# SCH_YDS-Charger_2022-05-27.net
KiCad netlist of a schematic drawn in EasyEDA
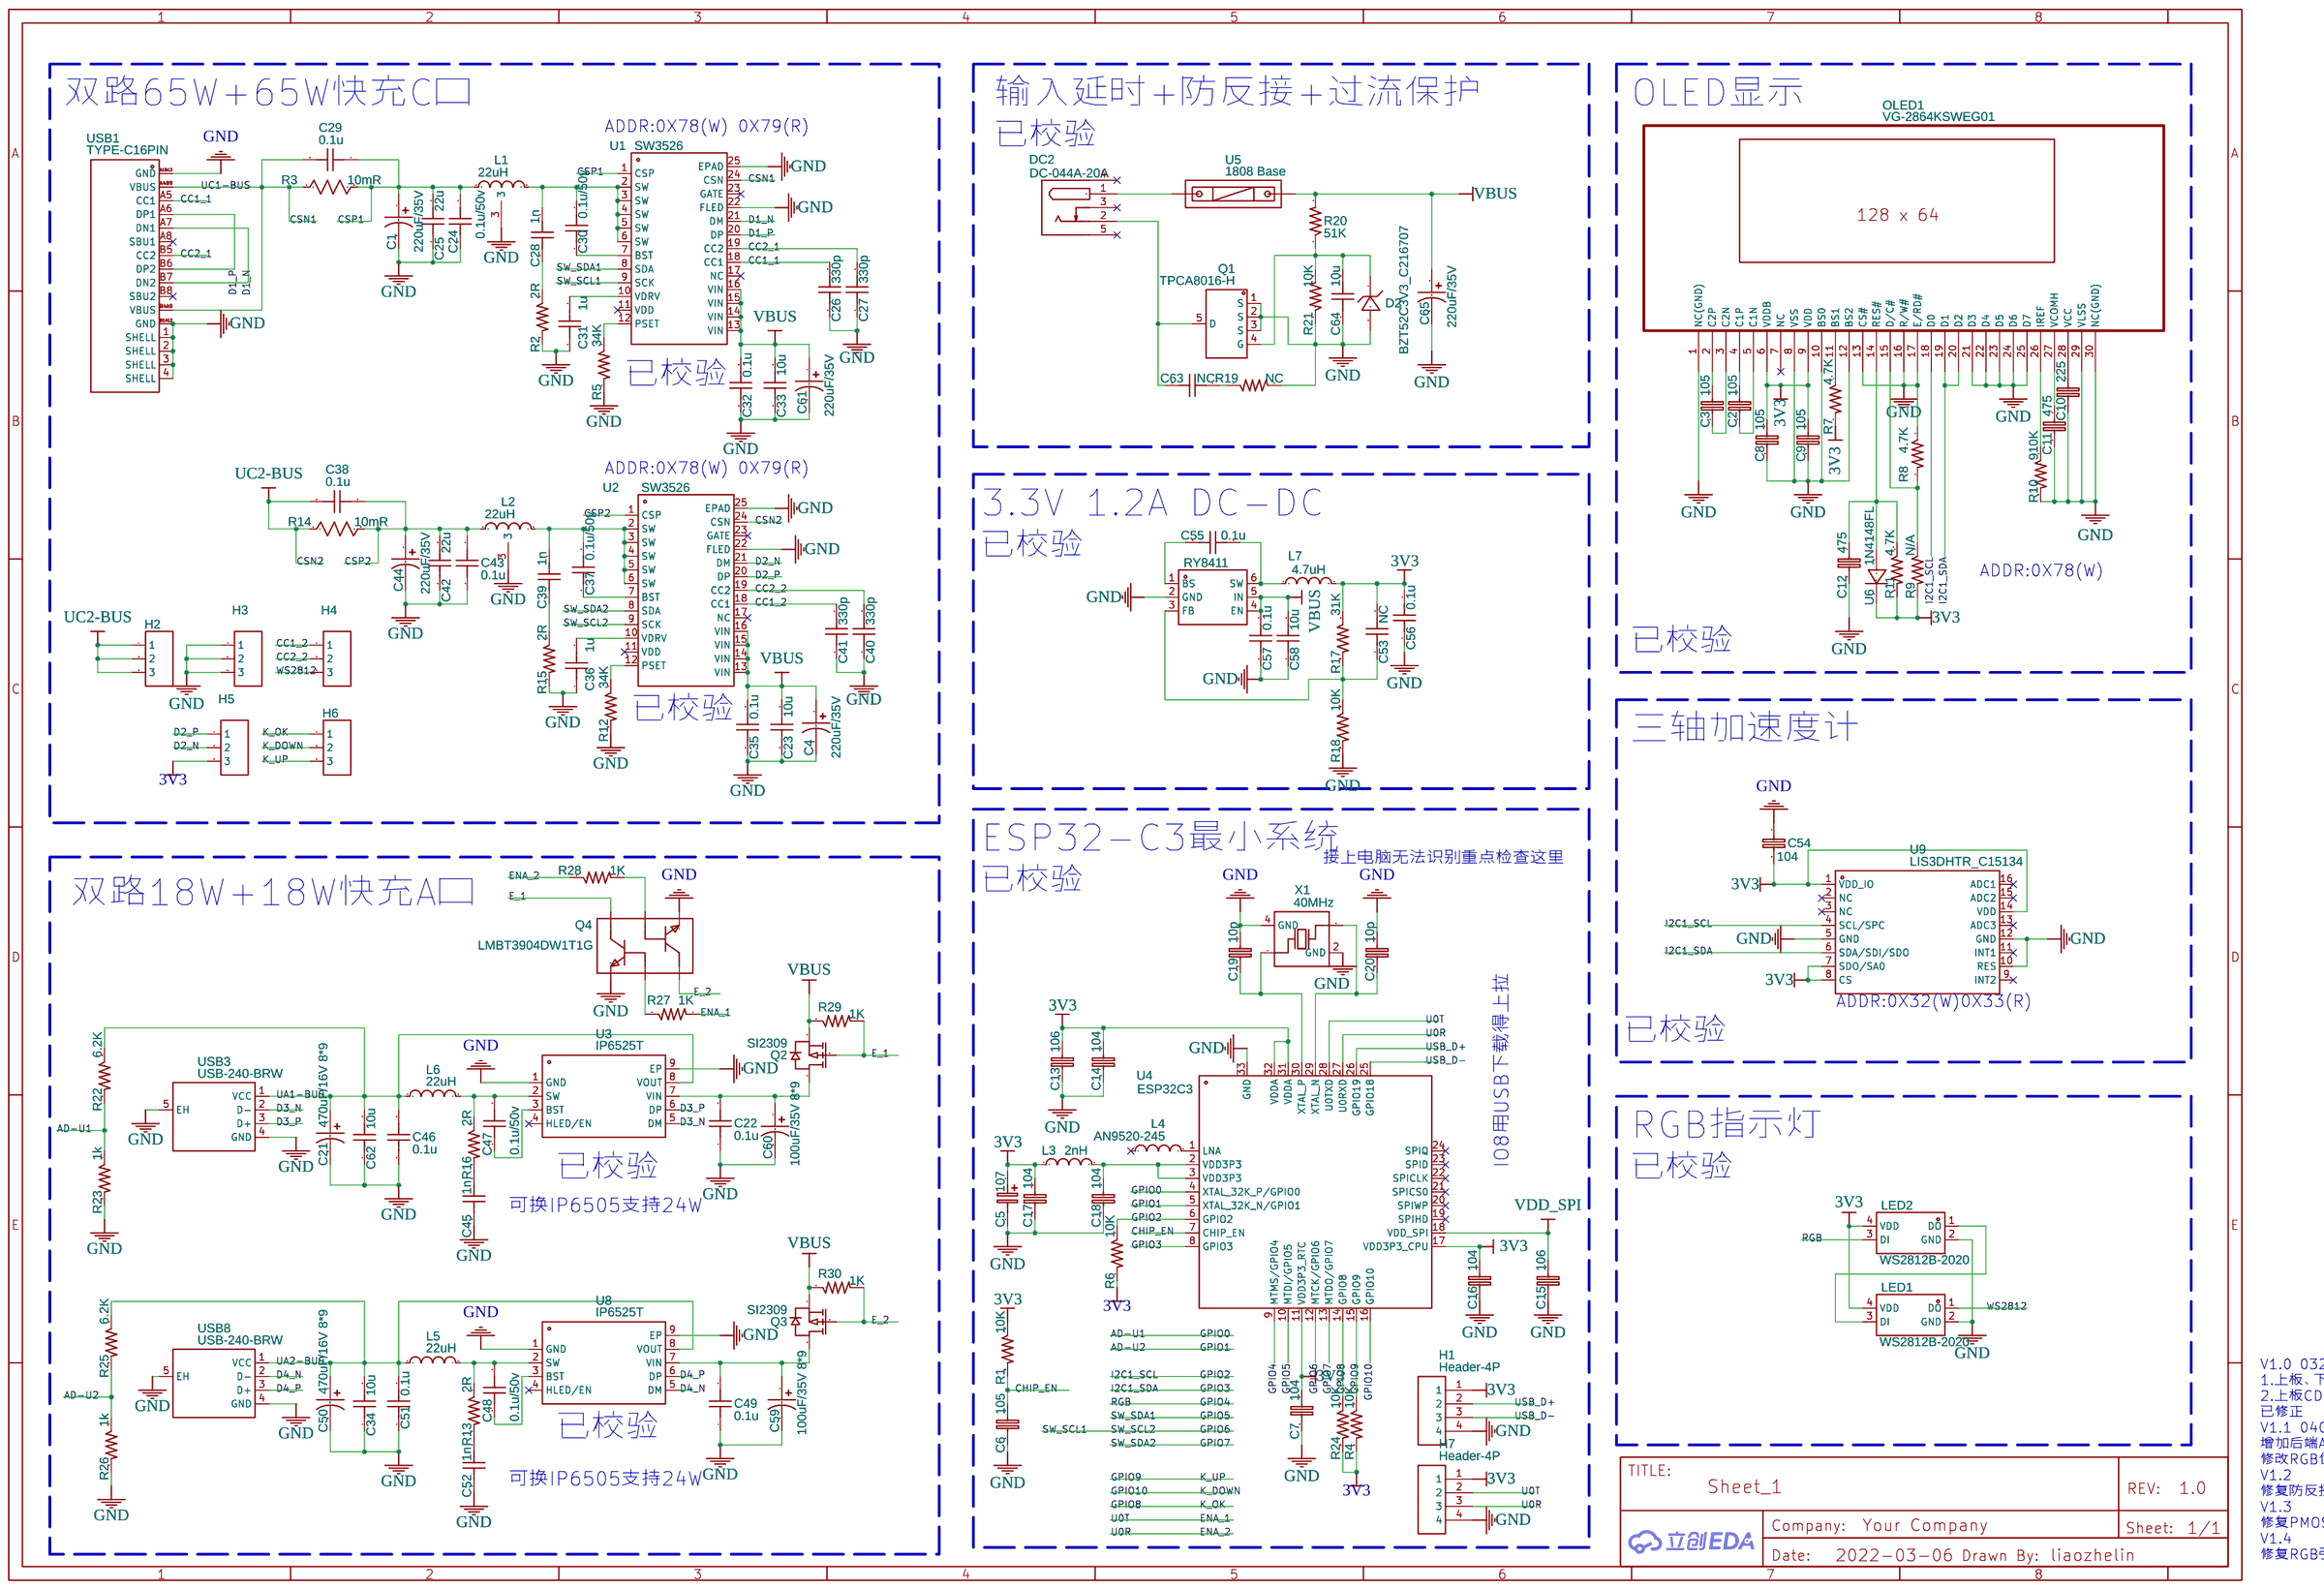
[diagram p0: schematic sheet]

(export (version "E")
  (design (tool "Eeschema 10.0.6"))
  (components
    (comp (ref "BS")
      (value "RY8411")
      (fields (field (name "BOM_Supplier Part") "C9900000347"))
      (libsource (lib "") (part "RY8411"))
    )
    (comp (ref "C1")
      (value "220uF/35V")
      (fields
        (field (name "BOM_Manufacturer Part") "BC016M821LO8*12L-1A4T")
        (field (name "BOM_Supplier Part") "C516110")
      )
      (libsource (lib "") (part "BC016M821LO8*12L-1A4T_1"))
    )
    (comp (ref "C2") (value "105") (libsource (lib "") (part "1.0PF-50V(-_+.25PF)(0603)")))
    (comp (ref "C3") (value "105") (libsource (lib "") (part "1.0PF-50V(-_+.25PF)(0603)")))
    (comp (ref "C4")
      (value "220uF/35V")
      (fields
        (field (name "BOM_Manufacturer Part") "BC016M821LO8*12L-1A4T")
        (field (name "BOM_Supplier Part") "C516110")
      )
      (libsource (lib "") (part "BC016M821LO8*12L-1A4T_1"))
    )
    (comp (ref "C5") (value "107") (libsource (lib "") (part "C_Tan_SMD_B_EU")))
    (comp (ref "C6") (value "105") (libsource (lib "") (part "1.0PF-50V(-_+.25PF)(0603)")))
    (comp (ref "C7") (value "104") (libsource (lib "") (part "1.0PF-50V(-_+.25PF)(0603)")))
    (comp (ref "C8") (value "105") (libsource (lib "") (part "1.0PF-50V(-_+.25PF)(0603)")))
    (comp (ref "C9") (value "105") (libsource (lib "") (part "1.0PF-50V(-_+.25PF)(0603)")))
    (comp (ref "C10") (value "225") (libsource (lib "") (part "1.0PF-50V(-_+.25PF)(0603)")))
    (comp (ref "C11") (value "475") (libsource (lib "") (part "1.0PF-50V(-_+.25PF)(0603)")))
    (comp (ref "C12") (value "475") (libsource (lib "") (part "1.0PF-50V(-_+.25PF)(0603)")))
    (comp (ref "C13") (value "106") (libsource (lib "") (part "1.0PF-50V(-_+.25PF)(0603)")))
    (comp (ref "C14") (value "104") (libsource (lib "") (part "1.0PF-50V(-_+.25PF)(0603)")))
    (comp (ref "C15") (value "106") (libsource (lib "") (part "1.0PF-50V(-_+.25PF)(0603)")))
    (comp (ref "C16") (value "104") (libsource (lib "") (part "1.0PF-50V(-_+.25PF)(0603)")))
    (comp (ref "C17") (value "104") (libsource (lib "") (part "1.0PF-50V(-_+.25PF)(0603)")))
    (comp (ref "C18") (value "104") (libsource (lib "") (part "1.0PF-50V(-_+.25PF)(0603)")))
    (comp (ref "C19") (value "10p") (libsource (lib "") (part "1.0PF-50V(-_+.25PF)(0603)")))
    (comp (ref "C20") (value "10p") (libsource (lib "") (part "1.0PF-50V(-_+.25PF)(0603)")))
    (comp (ref "C21")
      (value "470uF/16V 8*9")
      (fields
        (field (name "BOM_Manufacturer Part") "BC016M821LO8*12L-1A4T")
        (field (name "BOM_Supplier Part") "C516110")
      )
      (libsource (lib "") (part "BC016M821LO8*12L-1A4T"))
    )
    (comp (ref "C22") (value "0.1u") (libsource (lib "") (part "C_0805_US")))
    (comp (ref "C23") (value "10u") (libsource (lib "") (part "C_0805_US")))
    (comp (ref "C24") (value "0.1u/50v") (libsource (lib "") (part "C_0805_US")))
    (comp (ref "C25") (value "22u") (libsource (lib "") (part "C_0805_US")))
    (comp (ref "C26") (value "330p") (libsource (lib "") (part "C_0805_US")))
    (comp (ref "C27") (value "330p") (libsource (lib "") (part "C_0805_US")))
    (comp (ref "C28") (value "1n") (libsource (lib "") (part "C_0805_US")))
    (comp (ref "C29") (value "0.1u") (libsource (lib "") (part "C_0805_US_1")))
    (comp (ref "C30") (value "0.1u/50v") (libsource (lib "") (part "C_0805_US")))
    (comp (ref "C31") (value "1u") (libsource (lib "") (part "C_0805_US")))
    (comp (ref "C32") (value "0.1u") (libsource (lib "") (part "C_0805_US")))
    (comp (ref "C33") (value "10u") (libsource (lib "") (part "C_0805_US")))
    (comp (ref "C34") (value "10u") (libsource (lib "") (part "C_0805_US")))
    (comp (ref "C35") (value "0.1u") (libsource (lib "") (part "C_0805_US")))
    (comp (ref "C36") (value "1u") (libsource (lib "") (part "C_0805_US")))
    (comp (ref "C37") (value "0.1u/50v") (libsource (lib "") (part "C_0805_US")))
    (comp (ref "C38") (value "0.1u") (libsource (lib "") (part "C_0805_US_1")))
    (comp (ref "C39") (value "1n") (libsource (lib "") (part "C_0805_US")))
    (comp (ref "C40") (value "330p") (libsource (lib "") (part "C_0805_US")))
    (comp (ref "C41") (value "330p") (libsource (lib "") (part "C_0805_US")))
    (comp (ref "C42") (value "22u") (libsource (lib "") (part "C_0805_US")))
    (comp (ref "C43") (value "0.1u") (libsource (lib "") (part "C_0805_US")))
    (comp (ref "C44")
      (value "220uF/35V")
      (fields
        (field (name "BOM_Manufacturer Part") "BC016M821LO8*12L-1A4T")
        (field (name "BOM_Supplier Part") "C516110")
      )
      (libsource (lib "") (part "BC016M821LO8*12L-1A4T_1"))
    )
    (comp (ref "C45") (value "1n") (libsource (lib "") (part "C_0805_US")))
    (comp (ref "C46") (value "0.1u") (libsource (lib "") (part "C_0805_US")))
    (comp (ref "C47") (value "0.1u/50v") (libsource (lib "") (part "C_0805_US")))
    (comp (ref "C48") (value "0.1u/50v") (libsource (lib "") (part "C_0805_US")))
    (comp (ref "C49") (value "0.1u") (libsource (lib "") (part "C_0805_US")))
    (comp (ref "C50")
      (value "470uF/16V 8*9")
      (fields
        (field (name "BOM_Manufacturer Part") "BC016M821LO8*12L-1A4T")
        (field (name "BOM_Supplier Part") "C516110")
      )
      (libsource (lib "") (part "BC016M821LO8*12L-1A4T"))
    )
    (comp (ref "C51") (value "0.1u") (libsource (lib "") (part "C_0805_US")))
    (comp (ref "C52") (value "1n") (libsource (lib "") (part "C_0805_US")))
    (comp (ref "C53") (value "NC") (libsource (lib "") (part "C_0805_US")))
    (comp (ref "C54") (value "104") (libsource (lib "") (part "1.0PF-50V(-_+.25PF)(0603)")))
    (comp (ref "C55") (value "0.1u") (libsource (lib "") (part "C_0805_US_1")))
    (comp (ref "C56") (value "0.1u") (libsource (lib "") (part "C_0805_US")))
    (comp (ref "C57") (value "0.1u") (libsource (lib "") (part "C_0805_US_2")))
    (comp (ref "C58") (value "10u") (libsource (lib "") (part "C_0805_US")))
    (comp (ref "C59")
      (value "100uF/35V 8*9")
      (fields
        (field (name "BOM_Manufacturer Part") "BC016M821LO8*12L-1A4T")
        (field (name "BOM_Supplier Part") "C516110")
      )
      (libsource (lib "") (part "BC016M821LO8*12L-1A4T_2"))
    )
    (comp (ref "C60")
      (value "100uF/35V 8*9")
      (fields
        (field (name "BOM_Manufacturer Part") "BC016M821LO8*12L-1A4T")
        (field (name "BOM_Supplier Part") "C516110")
      )
      (libsource (lib "") (part "BC016M821LO8*12L-1A4T_2"))
    )
    (comp (ref "C61")
      (value "220uF/35V")
      (fields
        (field (name "BOM_Manufacturer Part") "BC016M821LO8*12L-1A4T")
        (field (name "BOM_Supplier Part") "C516110")
      )
      (libsource (lib "") (part "BC016M821LO8*12L-1A4T_1"))
    )
    (comp (ref "C62") (value "10u") (libsource (lib "") (part "C_0805_US")))
    (comp (ref "C63") (value "NC") (libsource (lib "") (part "C_0805_US_1")))
    (comp (ref "C64") (value "10u") (libsource (lib "") (part "C_0805_US")))
    (comp (ref "C65")
      (value "220uF/35V")
      (fields
        (field (name "BOM_Manufacturer Part") "BC016M821LO8*12L-1A4T")
        (field (name "BOM_Supplier Part") "C516110")
      )
      (libsource (lib "") (part "BC016M821LO8*12L-1A4T_3"))
    )
    (comp (ref "D2")
      (value "BZT52C3V3_C216707")
      (fields (field (name "BOM_Manufacturer Part") "BZT52C3V3") (field (name "BOM_Supplier Part") "C216707"))
      (libsource (lib "") (part "BZT52C3V3_C216707"))
    )
    (comp (ref "DC2")
      (value "DC-044A-20A")
      (fields (field (name "BOM_Supplier Part") "C129006"))
      (libsource (lib "") (part "DC-044A-20A"))
    )
    (comp (ref "H1") (value "Header-4P") (libsource (lib "") (part "Header-4P")))
    (comp (ref "H2")
      (value "HDR-F-2.54_1x3")
      (fields (field (name "BOM_Supplier Part") "C146690"))
      (libsource (lib "") (part "HDR-F-2.54_1x3"))
    )
    (comp (ref "H3")
      (value "HDR-F-2.54_1x3")
      (fields (field (name "BOM_Supplier Part") "C146690"))
      (libsource (lib "") (part "HDR-F-2.54_1x3"))
    )
    (comp (ref "H4")
      (value "HDR-F-2.54_1x3")
      (fields (field (name "BOM_Supplier Part") "C146690"))
      (libsource (lib "") (part "HDR-F-2.54_1x3"))
    )
    (comp (ref "H5")
      (value "HDR-F-2.54_1x3")
      (fields (field (name "BOM_Supplier Part") "C146690"))
      (libsource (lib "") (part "HDR-F-2.54_1x3"))
    )
    (comp (ref "H6")
      (value "HDR-F-2.54_1x3")
      (fields (field (name "BOM_Supplier Part") "C146690"))
      (libsource (lib "") (part "HDR-F-2.54_1x3"))
    )
    (comp (ref "H7") (value "Header-4P") (libsource (lib "") (part "Header-4P")))
    (comp (ref "L1")
      (value "22uH")
      (fields
        (field (name "BOM_Manufacturer Part") "CDEP147NP-6R1MC-125")
        (field (name "BOM_Supplier Part") "C2455724")
      )
      (libsource (lib "") (part "CDEP147NP-6R1MC-125"))
    )
    (comp (ref "L2")
      (value "22uH")
      (fields
        (field (name "BOM_Manufacturer Part") "CDEP147NP-6R1MC-125")
        (field (name "BOM_Supplier Part") "C2455724")
      )
      (libsource (lib "") (part "CDEP147NP-6R1MC-125"))
    )
    (comp (ref "L3") (value "2nH") (libsource (lib "") (part "L0603_US")))
    (comp (ref "L4")
      (value "AN9520-245")
      (fields (field (name "BOM_Supplier Part") "C99665"))
      (libsource (lib "") (part "AN9520-245"))
    )
    (comp (ref "L5")
      (value "22uH")
      (fields
        (field (name "BOM_Manufacturer Part") "CDRH127NP-470MC")
        (field (name "BOM_Supplier Part") "C167265")
      )
      (libsource (lib "") (part "CDRH127NP-470MC"))
    )
    (comp (ref "L6")
      (value "22uH")
      (fields
        (field (name "BOM_Manufacturer Part") "CDRH127NP-470MC")
        (field (name "BOM_Supplier Part") "C167265")
      )
      (libsource (lib "") (part "CDRH127NP-470MC"))
    )
    (comp (ref "L7")
      (value "4.7uH")
      (fields
        (field (name "BOM_Manufacturer Part") "CD43(L)-10uH")
        (field (name "BOM_Supplier Part") "C9900005836")
      )
      (libsource (lib "") (part "CD43(L)-10UH"))
    )
    (comp (ref "LED1")
      (value "WS2812B-2020")
      (fields (field (name "BOM_Supplier Part") "C965555"))
      (libsource (lib "") (part "WS2812B-2020"))
    )
    (comp (ref "LED2")
      (value "WS2812B-2020")
      (fields (field (name "BOM_Supplier Part") "C965555"))
      (libsource (lib "") (part "WS2812B-2020"))
    )
    (comp (ref "OLED1")
      (value "VG-2864KSWEG01")
      (fields (field (name "BOM_Supplier Part") "C194313"))
      (libsource (lib "") (part "VG-2864KSWEG01"))
    )
    (comp (ref "Q1")
      (value "TPCA8016-H")
      (fields (field (name "BOM_Supplier Part") "C37805"))
      (libsource (lib "") (part "TPCA8016-H"))
    )
    (comp (ref "Q2")
      (value "SI2309")
      (fields
        (field (name "BOM_Manufacturer Part") "SI2309CDS-T1-E3")
        (field (name "BOM_Supplier Part") "C553975")
      )
      (libsource (lib "") (part "SI2309CDS-T1-E3_1"))
    )
    (comp (ref "Q3")
      (value "SI2309")
      (fields
        (field (name "BOM_Manufacturer Part") "SI2309CDS-T1-E3")
        (field (name "BOM_Supplier Part") "C553975")
      )
      (libsource (lib "") (part "SI2309CDS-T1-E3"))
    )
    (comp (ref "Q4")
      (value "LMBT3904DW1T1G")
      (fields (field (name "BOM_Supplier Part") "C131781"))
      (libsource (lib "") (part "LMBT3904DW1T1G"))
    )
    (comp (ref "R1") (value "10K") (libsource (lib "") (part "1.2MOHMS-1_10W-1%(0603)")))
    (comp (ref "R2") (value "2R") (libsource (lib "") (part "1.2MOHMS-1_10W-1%(0603)")))
    (comp (ref "R3") (value "10mR") (libsource (lib "") (part "R_1206_US")))
    (comp (ref "R4") (value "10K") (libsource (lib "") (part "1.2MOHMS-1_10W-1%(0603)")))
    (comp (ref "R5") (value "34K") (libsource (lib "") (part "1.2MOHMS-1_10W-1%(0603)")))
    (comp (ref "R6") (value "10K") (libsource (lib "") (part "1.2MOHMS-1_10W-1%(0603)")))
    (comp (ref "R7") (value "4.7K") (libsource (lib "") (part "1.2MOHMS-1_10W-1%(0603)")))
    (comp (ref "R8") (value "4.7K") (libsource (lib "") (part "1.2MOHMS-1_10W-1%(0603)")))
    (comp (ref "R9") (value "N/A") (libsource (lib "") (part "1.2MOHMS-1_10W-1%(0603)")))
    (comp (ref "R10") (value "910K") (libsource (lib "") (part "1.2MOHMS-1_10W-1%(0603)")))
    (comp (ref "R11") (value "4.7K") (libsource (lib "") (part "1.2MOHMS-1_10W-1%(0603)")))
    (comp (ref "R12") (value "34K") (libsource (lib "") (part "1.2MOHMS-1_10W-1%(0603)")))
    (comp (ref "R13") (value "2R") (libsource (lib "") (part "1.2MOHMS-1_10W-1%(0603)")))
    (comp (ref "R14") (value "10mR") (libsource (lib "") (part "R_1206_US")))
    (comp (ref "R15") (value "2R") (libsource (lib "") (part "1.2MOHMS-1_10W-1%(0603)")))
    (comp (ref "R16") (value "2R") (libsource (lib "") (part "1.2MOHMS-1_10W-1%(0603)")))
    (comp (ref "R17") (value "31K") (libsource (lib "") (part "1.2MOHMS-1_10W-1%(0603)")))
    (comp (ref "R18") (value "10K") (libsource (lib "") (part "1.2MOHMS-1_10W-1%(0603)")))
    (comp (ref "R19") (value "NC") (libsource (lib "") (part "1.2MOHMS-1_10W-1%(0603)_1")))
    (comp (ref "R20") (value "51K") (libsource (lib "") (part "1.2MOHMS-1_10W-1%(0603)_2")))
    (comp (ref "R21") (value "10K") (libsource (lib "") (part "1.2MOHMS-1_10W-1%(0603)_2")))
    (comp (ref "R22") (value "6.2K") (libsource (lib "") (part "1.2MOHMS-1_10W-1%(0603)")))
    (comp (ref "R23") (value "1k") (libsource (lib "") (part "1.2MOHMS-1_10W-1%(0603)")))
    (comp (ref "R24") (value "10K") (libsource (lib "") (part "1.2MOHMS-1_10W-1%(0603)")))
    (comp (ref "R25") (value "6.2K") (libsource (lib "") (part "1.2MOHMS-1_10W-1%(0603)")))
    (comp (ref "R26") (value "1k") (libsource (lib "") (part "1.2MOHMS-1_10W-1%(0603)")))
    (comp (ref "R27") (value "1K") (libsource (lib "") (part "1.2MOHMS-1_10W-1%(0603)_1")))
    (comp (ref "R28") (value "1K") (libsource (lib "") (part "1.2MOHMS-1_10W-1%(0603)_1")))
    (comp (ref "R29") (value "1K") (libsource (lib "") (part "1.2MOHMS-1_10W-1%(0603)_1")))
    (comp (ref "R30") (value "1K") (libsource (lib "") (part "1.2MOHMS-1_10W-1%(0603)_1")))
    (comp (ref "U1")
      (value "SW3526")
      (fields (field (name "BOM_Supplier Part") "C2912236"))
      (libsource (lib "") (part "SW3526"))
    )
    (comp (ref "U2")
      (value "SW3526")
      (fields (field (name "BOM_Supplier Part") "C2912236"))
      (libsource (lib "") (part "SW3526"))
    )
    (comp (ref "U3")
      (value "IP6525T")
      (fields (field (name "BOM_Supplier Part") "C432573"))
      (libsource (lib "") (part "IP6525T"))
    )
    (comp (ref "U4")
      (value "ESP32C3")
      (fields (field (name "BOM_Supplier Part") "C77967"))
      (libsource (lib "") (part "ESP32C3"))
    )
    (comp (ref "U5")
      (value "1808 Base")
      (fields (field (name "BOM_Supplier Part") "C3133"))
      (libsource (lib "") (part "1808 Base"))
    )
    (comp (ref "U6")
      (value "1N4148FL")
      (fields (field (name "BOM_Supplier Part") "C2874197"))
      (libsource (lib "") (part "1N4148FL"))
    )
    (comp (ref "U8")
      (value "IP6525T")
      (fields (field (name "BOM_Supplier Part") "C432573"))
      (libsource (lib "") (part "IP6525T"))
    )
    (comp (ref "U9")
      (value "LIS3DHTR_C15134")
      (fields (field (name "BOM_Manufacturer Part") "LIS3DHTR") (field (name "BOM_Supplier Part") "C15134"))
      (libsource (lib "") (part "LIS3DHTR_C15134"))
    )
    (comp (ref "USB1")
      (value "TYPE-C16PIN")
      (fields (field (name "BOM_Supplier Part") "C393939"))
      (libsource (lib "") (part "TYPE-C16PIN"))
    )
    (comp (ref "USB3")
      (value "USB-240-BRW")
      (fields (field (name "BOM_Supplier Part") "C720530"))
      (libsource (lib "") (part "USB-240-BRW"))
    )
    (comp (ref "USB8")
      (value "USB-240-BRW")
      (fields (field (name "BOM_Supplier Part") "C720530"))
      (libsource (lib "") (part "USB-240-BRW"))
    )
    (comp (ref "X1")
      (value "40MHz")
      (fields
        (field (name "BOM_Manufacturer Part") "SX32Y040000BF1T")
        (field (name "BOM_Supplier Part") "C271642")
      )
      (libsource (lib "") (part "SX32Y040000BF1T"))
    )
  )
  (nets
    (net (code "1") (name "/AD-U1") (class "Default")
      (node (ref "R22") (pin "2") (pinfunction "2_2") (pintype "unspecified"))
      (node (ref "R23") (pin "1") (pinfunction "1_1") (pintype "unspecified"))
      (node (ref "U4") (pin "4") (pinfunction "XTAL_32K_P/GPIO0_4") (pintype "unspecified"))
    )
    (net (code "2") (name "/AD-U2") (class "Default")
      (node (ref "R25") (pin "2") (pinfunction "2_2") (pintype "unspecified"))
      (node (ref "R26") (pin "1") (pinfunction "1_1") (pintype "unspecified"))
      (node (ref "U4") (pin "5") (pinfunction "XTAL_32K_N/GPIO1_5") (pintype "unspecified"))
    )
    (net (code "3") (name "/CC1_1") (class "Default")
      (node (ref "C26") (pin "2") (pinfunction "2_2") (pintype "unspecified"))
      (node (ref "U1") (pin "18") (pinfunction "CC1_18") (pintype "unspecified"))
      (node (ref "USB1") (pin "A5") (pinfunction "CC1_A5") (pintype "unspecified"))
    )
    (net (code "4") (name "/CC1_2") (class "Default")
      (node (ref "C41") (pin "2") (pinfunction "2_2") (pintype "unspecified"))
      (node (ref "H4") (pin "1") (pinfunction "1_1") (pintype "input"))
      (node (ref "U2") (pin "18") (pinfunction "CC1_18") (pintype "unspecified"))
    )
    (net (code "5") (name "/CC2_1") (class "Default")
      (node (ref "C27") (pin "2") (pinfunction "2_2") (pintype "unspecified"))
      (node (ref "U1") (pin "19") (pinfunction "CC2_19") (pintype "unspecified"))
      (node (ref "USB1") (pin "B5") (pinfunction "CC2_B5") (pintype "unspecified"))
    )
    (net (code "6") (name "/CC2_2") (class "Default")
      (node (ref "C40") (pin "2") (pinfunction "2_2") (pintype "unspecified"))
      (node (ref "H4") (pin "2") (pinfunction "2_2") (pintype "input"))
      (node (ref "U2") (pin "19") (pinfunction "CC2_19") (pintype "unspecified"))
    )
    (net (code "7") (name "/CHIP_EN") (class "Default")
      (node (ref "C6") (pin "1") (pinfunction "1_1") (pintype "unspecified"))
      (node (ref "R1") (pin "2") (pinfunction "2_2") (pintype "unspecified"))
      (node (ref "U4") (pin "7") (pinfunction "CHIP_EN_7") (pintype "unspecified"))
    )
    (net (code "8") (name "/CSN1") (class "Default")
      (node (ref "C29") (pin "2") (pinfunction "2_2") (pintype "unspecified"))
      (node (ref "R3") (pin "1") (pinfunction "1_1") (pintype "unspecified"))
      (node (ref "U1") (pin "24") (pinfunction "CSN_24") (pintype "unspecified"))
      (node (ref "USB1") (pin "A4B9") (pinfunction "VBUS_A4B9") (pintype "unspecified"))
      (node (ref "USB1") (pin "B4A9") (pinfunction "VBUS_B4A9") (pintype "unspecified"))
    )
    (net (code "9") (name "/CSP1") (class "Default")
      (node (ref "C1") (pin "1") (pinfunction "1_1") (pintype "unspecified"))
      (node (ref "C24") (pin "2") (pinfunction "2_2") (pintype "unspecified"))
      (node (ref "C25") (pin "2") (pinfunction "2_2") (pintype "unspecified"))
      (node (ref "C29") (pin "1") (pinfunction "1_1") (pintype "unspecified"))
      (node (ref "L1") (pin "2") (pinfunction "2_2") (pintype "unspecified"))
      (node (ref "R3") (pin "2") (pinfunction "2_2") (pintype "unspecified"))
      (node (ref "U1") (pin "1") (pinfunction "CSP_1") (pintype "unspecified"))
    )
    (net (code "10") (name "/CSP2") (class "Default")
      (node (ref "C38") (pin "1") (pinfunction "1_1") (pintype "unspecified"))
      (node (ref "C42") (pin "2") (pinfunction "2_2") (pintype "unspecified"))
      (node (ref "C43") (pin "2") (pinfunction "2_2") (pintype "unspecified"))
      (node (ref "C44") (pin "1") (pinfunction "1_1") (pintype "unspecified"))
      (node (ref "L2") (pin "2") (pinfunction "2_2") (pintype "unspecified"))
      (node (ref "R14") (pin "2") (pinfunction "2_2") (pintype "unspecified"))
      (node (ref "U2") (pin "1") (pinfunction "CSP_1") (pintype "unspecified"))
    )
    (net (code "11") (name "/D1_N") (class "Default")
      (node (ref "U1") (pin "21") (pinfunction "DM_21") (pintype "unspecified"))
      (node (ref "USB1") (pin "A7") (pinfunction "DN1_A7") (pintype "unspecified"))
      (node (ref "USB1") (pin "B7") (pinfunction "DN2_B7") (pintype "unspecified"))
    )
    (net (code "12") (name "/D1_P") (class "Default")
      (node (ref "U1") (pin "20") (pinfunction "DP_20") (pintype "unspecified"))
      (node (ref "USB1") (pin "A6") (pinfunction "DP1_A6") (pintype "unspecified"))
      (node (ref "USB1") (pin "B6") (pinfunction "DP2_B6") (pintype "unspecified"))
    )
    (net (code "13") (name "/D2_N") (class "Default")
      (node (ref "H5") (pin "2") (pinfunction "2_2") (pintype "input"))
      (node (ref "U2") (pin "21") (pinfunction "DM_21") (pintype "unspecified"))
    )
    (net (code "14") (name "/D2_P") (class "Default")
      (node (ref "H5") (pin "1") (pinfunction "1_1") (pintype "input"))
      (node (ref "U2") (pin "20") (pinfunction "DP_20") (pintype "unspecified"))
    )
    (net (code "15") (name "/D3_N") (class "Default")
      (node (ref "U3") (pin "5") (pinfunction "DM_5") (pintype "unspecified"))
      (node (ref "USB3") (pin "2") (pinfunction "D-_2") (pintype "input"))
    )
    (net (code "16") (name "/D3_P") (class "Default")
      (node (ref "U3") (pin "6") (pinfunction "DP_6") (pintype "unspecified"))
      (node (ref "USB3") (pin "3") (pinfunction "D+_3") (pintype "input"))
    )
    (net (code "17") (name "/D4_N") (class "Default")
      (node (ref "U8") (pin "5") (pinfunction "DM_5") (pintype "unspecified"))
      (node (ref "USB8") (pin "2") (pinfunction "D-_2") (pintype "input"))
    )
    (net (code "18") (name "/D4_P") (class "Default")
      (node (ref "U8") (pin "6") (pinfunction "DP_6") (pintype "unspecified"))
      (node (ref "USB8") (pin "3") (pinfunction "D+_3") (pintype "input"))
    )
    (net (code "19") (name "/ENA_1") (class "Default")
      (node (ref "H7") (pin "2") (pinfunction "2_2") (pintype "unspecified"))
      (node (ref "R27") (pin "2") (pinfunction "2_2") (pintype "unspecified"))
      (node (ref "U4") (pin "28") (pinfunction "U0TXD_28") (pintype "unspecified"))
    )
    (net (code "20") (name "/ENA_2") (class "Default")
      (node (ref "H7") (pin "3") (pinfunction "3_3") (pintype "unspecified"))
      (node (ref "R28") (pin "1") (pinfunction "1_1") (pintype "unspecified"))
      (node (ref "U4") (pin "27") (pinfunction "U0RXD_27") (pintype "unspecified"))
    )
    (net (code "21") (name "/E_1") (class "Default")
      (node (ref "Q2") (pin "1") (pinfunction "G_1") (pintype "unspecified"))
      (node (ref "Q4") (pin "6") (pinfunction "C_6") (pintype "unspecified"))
      (node (ref "R29") (pin "2") (pinfunction "2_2") (pintype "unspecified"))
    )
    (net (code "22") (name "/E_2") (class "Default")
      (node (ref "Q3") (pin "1") (pinfunction "G_1") (pintype "unspecified"))
      (node (ref "Q4") (pin "3") (pinfunction "C_3") (pintype "unspecified"))
      (node (ref "R30") (pin "2") (pinfunction "2_2") (pintype "unspecified"))
    )
    (net (code "23") (name "/GPIO2") (class "Default")
      (node (ref "OLED1") (pin "18") (pinfunction "D0_18") (pintype "passive"))
      (node (ref "R6") (pin "1") (pinfunction "1_1") (pintype "unspecified"))
      (node (ref "U4") (pin "6") (pinfunction "GPIO2_6") (pintype "unspecified"))
      (node (ref "U9") (pin "4") (pinfunction "SCL/SPC_4") (pintype "unspecified"))
    )
    (net (code "24") (name "/GPIO3") (class "Default")
      (node (ref "OLED1") (pin "19") (pinfunction "D1_19") (pintype "passive"))
      (node (ref "OLED1") (pin "20") (pinfunction "D2_20") (pintype "passive"))
      (node (ref "U4") (pin "8") (pinfunction "GPIO3_8") (pintype "unspecified"))
      (node (ref "U9") (pin "6") (pinfunction "SDA/SDI/SDO_6") (pintype "unspecified"))
    )
    (net (code "25") (name "/GPIO4") (class "Default")
      (node (ref "LED2") (pin "3") (pinfunction "DI_3") (pintype "unspecified"))
      (node (ref "U4") (pin "9") (pinfunction "MTMS/GPIO4_9") (pintype "unspecified"))
    )
    (net (code "26") (name "/GPIO5") (class "Default")
      (node (ref "U1") (pin "8") (pinfunction "SDA_8") (pintype "unspecified"))
      (node (ref "U4") (pin "10") (pinfunction "MTDI/GPIO5_10") (pintype "unspecified"))
    )
    (net (code "27") (name "/GPIO6") (class "Default")
      (node (ref "U1") (pin "9") (pinfunction "SCK_9") (pintype "unspecified"))
      (node (ref "U2") (pin "9") (pinfunction "SCK_9") (pintype "unspecified"))
      (node (ref "U4") (pin "12") (pinfunction "MTCK/GPIO6_12") (pintype "unspecified"))
    )
    (net (code "28") (name "/GPIO7") (class "Default")
      (node (ref "U2") (pin "8") (pinfunction "SDA_8") (pintype "unspecified"))
      (node (ref "U4") (pin "13") (pinfunction "MTDO/GPIO7_13") (pintype "unspecified"))
    )
    (net (code "29") (name "/GPIO8") (class "Default")
      (node (ref "H6") (pin "1") (pinfunction "1_1") (pintype "input"))
      (node (ref "R24") (pin "1") (pinfunction "1_1") (pintype "unspecified"))
      (node (ref "U4") (pin "14") (pinfunction "GPIO8_14") (pintype "unspecified"))
    )
    (net (code "30") (name "/GPIO9") (class "Default")
      (node (ref "H6") (pin "3") (pinfunction "3_3") (pintype "input"))
      (node (ref "R4") (pin "1") (pinfunction "1_1") (pintype "unspecified"))
      (node (ref "U4") (pin "15") (pinfunction "GPIO9_15") (pintype "unspecified"))
    )
    (net (code "31") (name "/GPIO10") (class "Default")
      (node (ref "H6") (pin "2") (pinfunction "2_2") (pintype "input"))
      (node (ref "U4") (pin "16") (pinfunction "GPIO10_16") (pintype "unspecified"))
    )
    (net (code "32") (name "/UA1-BUS") (class "Default")
      (node (ref "C21") (pin "1") (pinfunction "1_1") (pintype "unspecified"))
      (node (ref "C46") (pin "2") (pinfunction "2_2") (pintype "unspecified"))
      (node (ref "C62") (pin "2") (pinfunction "2_2") (pintype "unspecified"))
      (node (ref "L6") (pin "1") (pinfunction "1_1") (pintype "unspecified"))
      (node (ref "R22") (pin "1") (pinfunction "1_1") (pintype "unspecified"))
      (node (ref "U3") (pin "8") (pinfunction "VOUT_8") (pintype "unspecified"))
      (node (ref "USB3") (pin "1") (pinfunction "VCC_1") (pintype "input"))
    )
    (net (code "33") (name "/UA2-BUS") (class "Default")
      (node (ref "C34") (pin "2") (pinfunction "2_2") (pintype "unspecified"))
      (node (ref "C50") (pin "1") (pinfunction "1_1") (pintype "unspecified"))
      (node (ref "C51") (pin "2") (pinfunction "2_2") (pintype "unspecified"))
      (node (ref "L5") (pin "1") (pinfunction "1_1") (pintype "unspecified"))
      (node (ref "R25") (pin "1") (pinfunction "1_1") (pintype "unspecified"))
      (node (ref "U8") (pin "8") (pinfunction "VOUT_8") (pintype "unspecified"))
      (node (ref "USB8") (pin "1") (pinfunction "VCC_1") (pintype "input"))
    )
    (net (code "34") (name "/USB_D+") (class "Default")
      (node (ref "H1") (pin "2") (pinfunction "2_2") (pintype "unspecified"))
      (node (ref "U4") (pin "26") (pinfunction "GPIO19_26") (pintype "unspecified"))
    )
    (net (code "35") (name "/USB_D-") (class "Default")
      (node (ref "H1") (pin "3") (pinfunction "3_3") (pintype "unspecified"))
      (node (ref "U4") (pin "25") (pinfunction "GPIO18_25") (pintype "unspecified"))
    )
    (net (code "36") (name "/WS2812") (class "Default")
      (node (ref "H4") (pin "3") (pinfunction "3_3") (pintype "input"))
      (node (ref "LED1") (pin "1") (pinfunction "DO_1") (pintype "unspecified"))
    )
    (net (code "37") (name "3V3") (class "Default")
      (node (ref "C13") (pin "1") (pinfunction "1_1") (pintype "unspecified"))
      (node (ref "C14") (pin "1") (pinfunction "1_1") (pintype "unspecified"))
      (node (ref "C16") (pin "1") (pinfunction "1_1") (pintype "unspecified"))
      (node (ref "C17") (pin "1") (pinfunction "1_1") (pintype "unspecified"))
      (node (ref "C5") (pin "1") (pinfunction "1_1") (pintype "unspecified"))
      (node (ref "C53") (pin "2") (pinfunction "2_2") (pintype "unspecified"))
      (node (ref "C54") (pin "2") (pinfunction "2_2") (pintype "unspecified"))
      (node (ref "C56") (pin "2") (pinfunction "2_2") (pintype "unspecified"))
      (node (ref "C7") (pin "1") (pinfunction "1_1") (pintype "unspecified"))
      (node (ref "C8") (pin "1") (pinfunction "1_1") (pintype "unspecified"))
      (node (ref "C9") (pin "1") (pinfunction "1_1") (pintype "unspecified"))
      (node (ref "H1") (pin "1") (pinfunction "1_1") (pintype "unspecified"))
      (node (ref "H5") (pin "3") (pinfunction "3_3") (pintype "input"))
      (node (ref "H7") (pin "1") (pinfunction "1_1") (pintype "unspecified"))
      (node (ref "L3") (pin "1") (pinfunction "1_1") (pintype "unspecified"))
      (node (ref "L7") (pin "2") (pinfunction "2_2") (pintype "unspecified"))
      (node (ref "LED1") (pin "4") (pinfunction "VDD_4") (pintype "unspecified"))
      (node (ref "LED2") (pin "4") (pinfunction "VDD_4") (pintype "unspecified"))
      (node (ref "OLED1") (pin "6") (pinfunction "VDDB_6") (pintype "passive"))
      (node (ref "OLED1") (pin "9") (pinfunction "VDD_9") (pintype "passive"))
      (node (ref "R1") (pin "1") (pinfunction "1_1") (pintype "unspecified"))
      (node (ref "R11") (pin "2") (pinfunction "2_2") (pintype "unspecified"))
      (node (ref "R17") (pin "1") (pinfunction "1_1") (pintype "unspecified"))
      (node (ref "R24") (pin "2") (pinfunction "2_2") (pintype "unspecified"))
      (node (ref "R4") (pin "2") (pinfunction "2_2") (pintype "unspecified"))
      (node (ref "R6") (pin "2") (pinfunction "2_2") (pintype "unspecified"))
      (node (ref "R7") (pin "2") (pinfunction "2_2") (pintype "unspecified"))
      (node (ref "R9") (pin "2") (pinfunction "2_2") (pintype "unspecified"))
      (node (ref "U4") (pin "11") (pinfunction "VDD3P3_RTC_11") (pintype "unspecified"))
      (node (ref "U4") (pin "17") (pinfunction "VDD3P3_CPU_17") (pintype "unspecified"))
      (node (ref "U4") (pin "31") (pinfunction "VDDA_31") (pintype "unspecified"))
      (node (ref "U4") (pin "32") (pinfunction "VDDA_32") (pintype "unspecified"))
      (node (ref "U6") (pin "1") (pinfunction "C_1") (pintype "unspecified"))
      (node (ref "U9") (pin "1") (pinfunction "VDD_IO_1") (pintype "unspecified"))
      (node (ref "U9") (pin "14") (pinfunction "VDD_14") (pintype "unspecified"))
      (node (ref "U9") (pin "7") (pinfunction "SDO/SA0_7") (pintype "unspecified"))
      (node (ref "U9") (pin "8") (pinfunction "CS_8") (pintype "unspecified"))
    )
    (net (code "38") (name "GND") (class "Default")
      (node (ref "BS") (pin "2") (pinfunction "GND_2") (pintype "unspecified"))
      (node (ref "C1") (pin "2") (pinfunction "2_2") (pintype "unspecified"))
      (node (ref "C10") (pin "2") (pinfunction "2_2") (pintype "unspecified"))
      (node (ref "C11") (pin "2") (pinfunction "2_2") (pintype "unspecified"))
      (node (ref "C12") (pin "2") (pinfunction "2_2") (pintype "unspecified"))
      (node (ref "C13") (pin "2") (pinfunction "2_2") (pintype "unspecified"))
      (node (ref "C14") (pin "2") (pinfunction "2_2") (pintype "unspecified"))
      (node (ref "C15") (pin "2") (pinfunction "2_2") (pintype "unspecified"))
      (node (ref "C16") (pin "2") (pinfunction "2_2") (pintype "unspecified"))
      (node (ref "C17") (pin "2") (pinfunction "2_2") (pintype "unspecified"))
      (node (ref "C18") (pin "2") (pinfunction "2_2") (pintype "unspecified"))
      (node (ref "C19") (pin "1") (pinfunction "1_1") (pintype "unspecified"))
      (node (ref "C20") (pin "1") (pinfunction "1_1") (pintype "unspecified"))
      (node (ref "C21") (pin "2") (pinfunction "2_2") (pintype "unspecified"))
      (node (ref "C22") (pin "1") (pinfunction "1_1") (pintype "unspecified"))
      (node (ref "C23") (pin "1") (pinfunction "1_1") (pintype "unspecified"))
      (node (ref "C24") (pin "1") (pinfunction "1_1") (pintype "unspecified"))
      (node (ref "C25") (pin "1") (pinfunction "1_1") (pintype "unspecified"))
      (node (ref "C26") (pin "1") (pinfunction "1_1") (pintype "unspecified"))
      (node (ref "C27") (pin "1") (pinfunction "1_1") (pintype "unspecified"))
      (node (ref "C31") (pin "1") (pinfunction "1_1") (pintype "unspecified"))
      (node (ref "C32") (pin "1") (pinfunction "1_1") (pintype "unspecified"))
      (node (ref "C33") (pin "1") (pinfunction "1_1") (pintype "unspecified"))
      (node (ref "C34") (pin "1") (pinfunction "1_1") (pintype "unspecified"))
      (node (ref "C35") (pin "1") (pinfunction "1_1") (pintype "unspecified"))
      (node (ref "C36") (pin "1") (pinfunction "1_1") (pintype "unspecified"))
      (node (ref "C4") (pin "2") (pinfunction "2_2") (pintype "unspecified"))
      (node (ref "C40") (pin "1") (pinfunction "1_1") (pintype "unspecified"))
      (node (ref "C41") (pin "1") (pinfunction "1_1") (pintype "unspecified"))
      (node (ref "C42") (pin "1") (pinfunction "1_1") (pintype "unspecified"))
      (node (ref "C43") (pin "1") (pinfunction "1_1") (pintype "unspecified"))
      (node (ref "C44") (pin "2") (pinfunction "2_2") (pintype "unspecified"))
      (node (ref "C45") (pin "1") (pinfunction "1_1") (pintype "unspecified"))
      (node (ref "C46") (pin "1") (pinfunction "1_1") (pintype "unspecified"))
      (node (ref "C49") (pin "1") (pinfunction "1_1") (pintype "unspecified"))
      (node (ref "C5") (pin "2") (pinfunction "2_2") (pintype "unspecified"))
      (node (ref "C50") (pin "2") (pinfunction "2_2") (pintype "unspecified"))
      (node (ref "C51") (pin "1") (pinfunction "1_1") (pintype "unspecified"))
      (node (ref "C52") (pin "1") (pinfunction "1_1") (pintype "unspecified"))
      (node (ref "C54") (pin "1") (pinfunction "1_1") (pintype "unspecified"))
      (node (ref "C56") (pin "1") (pinfunction "1_1") (pintype "unspecified"))
      (node (ref "C57") (pin "2") (pinfunction "2_2") (pintype "unspecified"))
      (node (ref "C58") (pin "1") (pinfunction "1_1") (pintype "unspecified"))
      (node (ref "C59") (pin "2") (pinfunction "2_2") (pintype "unspecified"))
      (node (ref "C6") (pin "2") (pinfunction "2_2") (pintype "unspecified"))
      (node (ref "C60") (pin "2") (pinfunction "2_2") (pintype "unspecified"))
      (node (ref "C61") (pin "2") (pinfunction "2_2") (pintype "unspecified"))
      (node (ref "C62") (pin "1") (pinfunction "1_1") (pintype "unspecified"))
      (node (ref "C64") (pin "1") (pinfunction "1_1") (pintype "unspecified"))
      (node (ref "C65") (pin "2") (pinfunction "2_2") (pintype "unspecified"))
      (node (ref "C7") (pin "2") (pinfunction "2_2") (pintype "unspecified"))
      (node (ref "C8") (pin "2") (pinfunction "2_2") (pintype "unspecified"))
      (node (ref "C9") (pin "2") (pinfunction "2_2") (pintype "unspecified"))
      (node (ref "D2") (pin "2") (pinfunction "2_2") (pintype "unspecified"))
      (node (ref "H1") (pin "4") (pinfunction "4_4") (pintype "unspecified"))
      (node (ref "H3") (pin "1") (pinfunction "1_1") (pintype "input"))
      (node (ref "H3") (pin "2") (pinfunction "2_2") (pintype "input"))
      (node (ref "H3") (pin "3") (pinfunction "3_3") (pintype "input"))
      (node (ref "H7") (pin "4") (pinfunction "4_4") (pintype "unspecified"))
      (node (ref "L1") (pin "3") (pinfunction "3_3") (pintype "unspecified"))
      (node (ref "L2") (pin "3") (pinfunction "3_3") (pintype "unspecified"))
      (node (ref "LED1") (pin "2") (pinfunction "GND_2") (pintype "unspecified"))
      (node (ref "LED2") (pin "2") (pinfunction "GND_2") (pintype "unspecified"))
      (node (ref "OLED1") (pin "1") (pinfunction "NC(GND)_1") (pintype "passive"))
      (node (ref "OLED1") (pin "10") (pinfunction "BS0_10") (pintype "passive"))
      (node (ref "OLED1") (pin "12") (pinfunction "BS2_12") (pintype "passive"))
      (node (ref "OLED1") (pin "13") (pinfunction "CS#_13") (pintype "passive"))
      (node (ref "OLED1") (pin "16") (pinfunction "R/W#_16") (pintype "passive"))
      (node (ref "OLED1") (pin "17") (pinfunction "E/RD#_17") (pintype "passive"))
      (node (ref "OLED1") (pin "21") (pinfunction "D3_21") (pintype "passive"))
      (node (ref "OLED1") (pin "22") (pinfunction "D4_22") (pintype "passive"))
      (node (ref "OLED1") (pin "23") (pinfunction "D5_23") (pintype "passive"))
      (node (ref "OLED1") (pin "24") (pinfunction "D6_24") (pintype "passive"))
      (node (ref "OLED1") (pin "25") (pinfunction "D7_25") (pintype "passive"))
      (node (ref "OLED1") (pin "29") (pinfunction "VLSS_29") (pintype "passive"))
      (node (ref "OLED1") (pin "30") (pinfunction "NC(GND)_30") (pintype "passive"))
      (node (ref "OLED1") (pin "8") (pinfunction "VSS_8") (pintype "passive"))
      (node (ref "Q1") (pin "1") (pinfunction "S_1") (pintype "unspecified"))
      (node (ref "Q1") (pin "2") (pinfunction "S_2") (pintype "unspecified"))
      (node (ref "Q1") (pin "3") (pinfunction "S_3") (pintype "unspecified"))
      (node (ref "Q4") (pin "1") (pinfunction "E_1") (pintype "unspecified"))
      (node (ref "Q4") (pin "4") (pinfunction "E_4") (pintype "unspecified"))
      (node (ref "R10") (pin "2") (pinfunction "2_2") (pintype "unspecified"))
      (node (ref "R12") (pin "2") (pinfunction "2_2") (pintype "unspecified"))
      (node (ref "R15") (pin "2") (pinfunction "2_2") (pintype "unspecified"))
      (node (ref "R18") (pin "2") (pinfunction "2_2") (pintype "unspecified"))
      (node (ref "R19") (pin "2") (pinfunction "2_2") (pintype "unspecified"))
      (node (ref "R2") (pin "2") (pinfunction "2_2") (pintype "unspecified"))
      (node (ref "R21") (pin "1") (pinfunction "1_1") (pintype "unspecified"))
      (node (ref "R23") (pin "2") (pinfunction "2_2") (pintype "unspecified"))
      (node (ref "R26") (pin "2") (pinfunction "2_2") (pintype "unspecified"))
      (node (ref "R5") (pin "2") (pinfunction "2_2") (pintype "unspecified"))
      (node (ref "R8") (pin "1") (pinfunction "1_1") (pintype "unspecified"))
      (node (ref "U1") (pin "22") (pinfunction "FLED_22") (pintype "unspecified"))
      (node (ref "U1") (pin "25") (pinfunction "EPAD_25") (pintype "unspecified"))
      (node (ref "U2") (pin "22") (pinfunction "FLED_22") (pintype "unspecified"))
      (node (ref "U2") (pin "25") (pinfunction "EPAD_25") (pintype "unspecified"))
      (node (ref "U3") (pin "1") (pinfunction "GND_1") (pintype "unspecified"))
      (node (ref "U3") (pin "9") (pinfunction "EP_9") (pintype "unspecified"))
      (node (ref "U4") (pin "33") (pinfunction "GND_33") (pintype "unspecified"))
      (node (ref "U8") (pin "1") (pinfunction "GND_1") (pintype "unspecified"))
      (node (ref "U8") (pin "9") (pinfunction "EP_9") (pintype "unspecified"))
      (node (ref "U9") (pin "10") (pinfunction "RES_10") (pintype "unspecified"))
      (node (ref "U9") (pin "12") (pinfunction "GND_12") (pintype "unspecified"))
      (node (ref "U9") (pin "5") (pinfunction "GND_5") (pintype "unspecified"))
      (node (ref "USB1") (pin "1") (pinfunction "SHELL_1") (pintype "unspecified"))
      (node (ref "USB1") (pin "2") (pinfunction "SHELL_2") (pintype "unspecified"))
      (node (ref "USB1") (pin "3") (pinfunction "SHELL_3") (pintype "unspecified"))
      (node (ref "USB1") (pin "4") (pinfunction "SHELL_4") (pintype "unspecified"))
      (node (ref "USB1") (pin "A1B12") (pinfunction "GND_A1B12") (pintype "unspecified"))
      (node (ref "USB1") (pin "B1A12") (pinfunction "GND_B1A12") (pintype "unspecified"))
      (node (ref "USB3") (pin "4") (pinfunction "GND_4") (pintype "input"))
      (node (ref "USB3") (pin "5") (pinfunction "EH_5") (pintype "unspecified"))
      (node (ref "USB8") (pin "4") (pinfunction "GND_4") (pintype "input"))
      (node (ref "USB8") (pin "5") (pinfunction "EH_5") (pintype "unspecified"))
      (node (ref "X1") (pin "2") (pinfunction "GND_2") (pintype "input"))
      (node (ref "X1") (pin "4") (pinfunction "GND_4") (pintype "input"))
    )
    (net (code "39") (name "Net-(BS-BS)") (class "Default")
      (node (ref "BS") (pin "1") (pinfunction "BS_1") (pintype "unspecified"))
      (node (ref "C55") (pin "2") (pinfunction "2_2") (pintype "unspecified"))
    )
    (net (code "40") (name "Net-(BS-FB)") (class "Default")
      (node (ref "BS") (pin "3") (pinfunction "FB_3") (pintype "unspecified"))
      (node (ref "C53") (pin "1") (pinfunction "1_1") (pintype "unspecified"))
      (node (ref "R17") (pin "2") (pinfunction "2_2") (pintype "unspecified"))
      (node (ref "R18") (pin "1") (pinfunction "1_1") (pintype "unspecified"))
    )
    (net (code "41") (name "Net-(BS-SW)") (class "Default")
      (node (ref "BS") (pin "6") (pinfunction "SW_6") (pintype "unspecified"))
      (node (ref "C55") (pin "1") (pinfunction "1_1") (pintype "unspecified"))
      (node (ref "L7") (pin "1") (pinfunction "1_1") (pintype "unspecified"))
    )
    (net (code "42") (name "Net-(C18-Pad1)") (class "Default")
      (node (ref "C18") (pin "1") (pinfunction "1_1") (pintype "unspecified"))
      (node (ref "L3") (pin "2") (pinfunction "2_2") (pintype "unspecified"))
      (node (ref "U4") (pin "2") (pinfunction "VDD3P3_2") (pintype "unspecified"))
      (node (ref "U4") (pin "3") (pinfunction "VDD3P3_3") (pintype "unspecified"))
    )
    (net (code "43") (name "Net-(C28-Pad1)") (class "Default")
      (node (ref "C28") (pin "1") (pinfunction "1_1") (pintype "unspecified"))
      (node (ref "R2") (pin "1") (pinfunction "1_1") (pintype "unspecified"))
    )
    (net (code "44") (name "Net-(C28-Pad2)") (class "Default")
      (node (ref "C28") (pin "2") (pinfunction "2_2") (pintype "unspecified"))
      (node (ref "C30") (pin "2") (pinfunction "2_2") (pintype "unspecified"))
      (node (ref "L1") (pin "1") (pinfunction "1_1") (pintype "unspecified"))
      (node (ref "U1") (pin "2") (pinfunction "SW_2") (pintype "unspecified"))
      (node (ref "U1") (pin "3") (pinfunction "SW_3") (pintype "unspecified"))
      (node (ref "U1") (pin "4") (pinfunction "SW_4") (pintype "unspecified"))
      (node (ref "U1") (pin "5") (pinfunction "SW_5") (pintype "unspecified"))
      (node (ref "U1") (pin "6") (pinfunction "SW_6") (pintype "unspecified"))
    )
    (net (code "45") (name "Net-(C37-Pad2)") (class "Default")
      (node (ref "C37") (pin "2") (pinfunction "2_2") (pintype "unspecified"))
      (node (ref "C39") (pin "2") (pinfunction "2_2") (pintype "unspecified"))
      (node (ref "L2") (pin "1") (pinfunction "1_1") (pintype "unspecified"))
      (node (ref "U2") (pin "2") (pinfunction "SW_2") (pintype "unspecified"))
      (node (ref "U2") (pin "3") (pinfunction "SW_3") (pintype "unspecified"))
      (node (ref "U2") (pin "4") (pinfunction "SW_4") (pintype "unspecified"))
      (node (ref "U2") (pin "5") (pinfunction "SW_5") (pintype "unspecified"))
      (node (ref "U2") (pin "6") (pinfunction "SW_6") (pintype "unspecified"))
    )
    (net (code "46") (name "Net-(C39-Pad1)") (class "Default")
      (node (ref "C39") (pin "1") (pinfunction "1_1") (pintype "unspecified"))
      (node (ref "R15") (pin "1") (pinfunction "1_1") (pintype "unspecified"))
    )
    (net (code "47") (name "Net-(C45-Pad2)") (class "Default")
      (node (ref "C45") (pin "2") (pinfunction "2_2") (pintype "unspecified"))
      (node (ref "R16") (pin "2") (pinfunction "2_2") (pintype "unspecified"))
    )
    (net (code "48") (name "Net-(C52-Pad2)") (class "Default")
      (node (ref "C52") (pin "2") (pinfunction "2_2") (pintype "unspecified"))
      (node (ref "R13") (pin "2") (pinfunction "2_2") (pintype "unspecified"))
    )
    (net (code "49") (name "Net-(C63-Pad1)") (class "Default")
      (node (ref "C63") (pin "1") (pinfunction "1_1") (pintype "unspecified"))
      (node (ref "R19") (pin "1") (pinfunction "1_1") (pintype "unspecified"))
    )
    (net (code "50") (name "Net-(DC2-Pad1)") (class "Default")
      (node (ref "DC2") (pin "1") (pinfunction "1_1") (pintype "unspecified"))
      (node (ref "U5") (pin "1") (pinfunction "1_1") (pintype "unspecified"))
    )
    (net (code "51") (name "Net-(LED1-DI)") (class "Default")
      (node (ref "LED1") (pin "3") (pinfunction "DI_3") (pintype "unspecified"))
      (node (ref "LED2") (pin "1") (pinfunction "DO_1") (pintype "unspecified"))
    )
    (net (code "52") (name "Net-(OLED1-BS1)") (class "Default")
      (node (ref "OLED1") (pin "11") (pinfunction "BS1_11") (pintype "passive"))
      (node (ref "R7") (pin "1") (pinfunction "1_1") (pintype "unspecified"))
    )
    (net (code "53") (name "Net-(OLED1-C1N)") (class "Default")
      (node (ref "C2") (pin "2") (pinfunction "2_2") (pintype "unspecified"))
      (node (ref "OLED1") (pin "5") (pinfunction "C1N_5") (pintype "passive"))
    )
    (net (code "54") (name "Net-(OLED1-C1P)") (class "Default")
      (node (ref "C2") (pin "1") (pinfunction "1_1") (pintype "unspecified"))
      (node (ref "OLED1") (pin "4") (pinfunction "C1P_4") (pintype "passive"))
    )
    (net (code "55") (name "Net-(OLED1-C2N)") (class "Default")
      (node (ref "C3") (pin "2") (pinfunction "2_2") (pintype "unspecified"))
      (node (ref "OLED1") (pin "3") (pinfunction "C2N_3") (pintype "passive"))
    )
    (net (code "56") (name "Net-(OLED1-C2P)") (class "Default")
      (node (ref "C3") (pin "1") (pinfunction "1_1") (pintype "unspecified"))
      (node (ref "OLED1") (pin "2") (pinfunction "C2P_2") (pintype "passive"))
    )
    (net (code "57") (name "Net-(OLED1-D{slash}C#)") (class "Default")
      (node (ref "OLED1") (pin "15") (pinfunction "D/C#_15") (pintype "passive"))
      (node (ref "R8") (pin "2") (pinfunction "2_2") (pintype "unspecified"))
      (node (ref "R9") (pin "1") (pinfunction "1_1") (pintype "unspecified"))
    )
    (net (code "58") (name "Net-(OLED1-IREF)") (class "Default")
      (node (ref "OLED1") (pin "26") (pinfunction "IREF_26") (pintype "passive"))
      (node (ref "R10") (pin "1") (pinfunction "1_1") (pintype "unspecified"))
    )
    (net (code "59") (name "Net-(OLED1-RES#)") (class "Default")
      (node (ref "C12") (pin "1") (pinfunction "1_1") (pintype "unspecified"))
      (node (ref "OLED1") (pin "14") (pinfunction "RES#_14") (pintype "passive"))
      (node (ref "R11") (pin "1") (pinfunction "1_1") (pintype "unspecified"))
      (node (ref "U6") (pin "2") (pinfunction "A_2") (pintype "unspecified"))
    )
    (net (code "60") (name "Net-(OLED1-VCC)") (class "Default")
      (node (ref "C10") (pin "1") (pinfunction "1_1") (pintype "unspecified"))
      (node (ref "OLED1") (pin "28") (pinfunction "VCC_28") (pintype "passive"))
    )
    (net (code "61") (name "Net-(OLED1-VCOMH)") (class "Default")
      (node (ref "C11") (pin "1") (pinfunction "1_1") (pintype "unspecified"))
      (node (ref "OLED1") (pin "27") (pinfunction "VCOMH_27") (pintype "passive"))
    )
    (net (code "62") (name "Net-(Q1-D)") (class "Default")
      (node (ref "C63") (pin "2") (pinfunction "2_2") (pintype "unspecified"))
      (node (ref "DC2") (pin "2") (pinfunction "2_2") (pintype "unspecified"))
      (node (ref "Q1") (pin "5") (pinfunction "D_5") (pintype "unspecified"))
    )
    (net (code "63") (name "Net-(Q1-G)") (class "Default")
      (node (ref "C64") (pin "2") (pinfunction "2_2") (pintype "unspecified"))
      (node (ref "D2") (pin "1") (pinfunction "1_1") (pintype "unspecified"))
      (node (ref "Q1") (pin "4") (pinfunction "G_4") (pintype "unspecified"))
      (node (ref "R20") (pin "1") (pinfunction "1_1") (pintype "unspecified"))
      (node (ref "R21") (pin "2") (pinfunction "2_2") (pintype "unspecified"))
    )
    (net (code "64") (name "Net-(Q2-D)") (class "Default")
      (node (ref "C22") (pin "2") (pinfunction "2_2") (pintype "unspecified"))
      (node (ref "C60") (pin "1") (pinfunction "1_1") (pintype "unspecified"))
      (node (ref "Q2") (pin "3") (pinfunction "D_3") (pintype "unspecified"))
      (node (ref "U3") (pin "7") (pinfunction "VIN_7") (pintype "unspecified"))
    )
    (net (code "65") (name "Net-(Q3-D)") (class "Default")
      (node (ref "C49") (pin "2") (pinfunction "2_2") (pintype "unspecified"))
      (node (ref "C59") (pin "1") (pinfunction "1_1") (pintype "unspecified"))
      (node (ref "Q3") (pin "3") (pinfunction "D_3") (pintype "unspecified"))
      (node (ref "U8") (pin "7") (pinfunction "VIN_7") (pintype "unspecified"))
    )
    (net (code "66") (name "Net-(Q4-B-Pad2)") (class "Default")
      (node (ref "Q4") (pin "2") (pinfunction "B_2") (pintype "unspecified"))
      (node (ref "R27") (pin "1") (pinfunction "1_1") (pintype "unspecified"))
    )
    (net (code "67") (name "Net-(Q4-B-Pad5)") (class "Default")
      (node (ref "Q4") (pin "5") (pinfunction "B_5") (pintype "unspecified"))
      (node (ref "R28") (pin "2") (pinfunction "2_2") (pintype "unspecified"))
    )
    (net (code "68") (name "Net-(U1-BST)") (class "Default")
      (node (ref "C30") (pin "1") (pinfunction "1_1") (pintype "unspecified"))
      (node (ref "U1") (pin "7") (pinfunction "BST_7") (pintype "unspecified"))
    )
    (net (code "69") (name "Net-(U1-PSET)") (class "Default")
      (node (ref "R5") (pin "1") (pinfunction "1_1") (pintype "unspecified"))
      (node (ref "U1") (pin "12") (pinfunction "PSET_12") (pintype "unspecified"))
    )
    (net (code "70") (name "Net-(U1-VDRV)") (class "Default")
      (node (ref "C31") (pin "2") (pinfunction "2_2") (pintype "unspecified"))
      (node (ref "U1") (pin "10") (pinfunction "VDRV_10") (pintype "unspecified"))
    )
    (net (code "71") (name "Net-(U2-BST)") (class "Default")
      (node (ref "C37") (pin "1") (pinfunction "1_1") (pintype "unspecified"))
      (node (ref "U2") (pin "7") (pinfunction "BST_7") (pintype "unspecified"))
    )
    (net (code "72") (name "Net-(U2-PSET)") (class "Default")
      (node (ref "R12") (pin "1") (pinfunction "1_1") (pintype "unspecified"))
      (node (ref "U2") (pin "12") (pinfunction "PSET_12") (pintype "unspecified"))
    )
    (net (code "73") (name "Net-(U2-VDRV)") (class "Default")
      (node (ref "C36") (pin "2") (pinfunction "2_2") (pintype "unspecified"))
      (node (ref "U2") (pin "10") (pinfunction "VDRV_10") (pintype "unspecified"))
    )
    (net (code "74") (name "Net-(U3-BST)") (class "Default")
      (node (ref "C47") (pin "1") (pinfunction "1_1") (pintype "unspecified"))
      (node (ref "U3") (pin "3") (pinfunction "BST_3") (pintype "unspecified"))
    )
    (net (code "75") (name "Net-(U3-SW)") (class "Default")
      (node (ref "C47") (pin "2") (pinfunction "2_2") (pintype "unspecified"))
      (node (ref "L6") (pin "2") (pinfunction "2_2") (pintype "unspecified"))
      (node (ref "R16") (pin "1") (pinfunction "1_1") (pintype "unspecified"))
      (node (ref "U3") (pin "2") (pinfunction "SW_2") (pintype "unspecified"))
    )
    (net (code "76") (name "Net-(U4-LNA)") (class "Default")
      (node (ref "L4") (pin "1") (pinfunction "1_1") (pintype "unspecified"))
      (node (ref "U4") (pin "1") (pinfunction "LNA_1") (pintype "unspecified"))
    )
    (net (code "77") (name "Net-(U4-XTAL_N)") (class "Default")
      (node (ref "C20") (pin "2") (pinfunction "2_2") (pintype "unspecified"))
      (node (ref "U4") (pin "29") (pinfunction "XTAL_N_29") (pintype "unspecified"))
      (node (ref "X1") (pin "3") (pinfunction "OSC2_3") (pintype "input"))
    )
    (net (code "78") (name "Net-(U4-XTAL_P)") (class "Default")
      (node (ref "C19") (pin "2") (pinfunction "2_2") (pintype "unspecified"))
      (node (ref "U4") (pin "30") (pinfunction "XTAL_P_30") (pintype "unspecified"))
      (node (ref "X1") (pin "1") (pinfunction "OSC1_1") (pintype "input"))
    )
    (net (code "79") (name "Net-(U8-BST)") (class "Default")
      (node (ref "C48") (pin "1") (pinfunction "1_1") (pintype "unspecified"))
      (node (ref "U8") (pin "3") (pinfunction "BST_3") (pintype "unspecified"))
    )
    (net (code "80") (name "Net-(U8-SW)") (class "Default")
      (node (ref "C48") (pin "2") (pinfunction "2_2") (pintype "unspecified"))
      (node (ref "L5") (pin "2") (pinfunction "2_2") (pintype "unspecified"))
      (node (ref "R13") (pin "1") (pinfunction "1_1") (pintype "unspecified"))
      (node (ref "U8") (pin "2") (pinfunction "SW_2") (pintype "unspecified"))
    )
    (net (code "81") (name "UC2-BUS") (class "Default")
      (node (ref "C38") (pin "2") (pinfunction "2_2") (pintype "unspecified"))
      (node (ref "H2") (pin "1") (pinfunction "1_1") (pintype "input"))
      (node (ref "H2") (pin "2") (pinfunction "2_2") (pintype "input"))
      (node (ref "H2") (pin "3") (pinfunction "3_3") (pintype "input"))
      (node (ref "R14") (pin "1") (pinfunction "1_1") (pintype "unspecified"))
      (node (ref "U2") (pin "24") (pinfunction "CSN_24") (pintype "unspecified"))
    )
    (net (code "82") (name "VBUS") (class "Default")
      (node (ref "BS") (pin "4") (pinfunction "EN_4") (pintype "unspecified"))
      (node (ref "BS") (pin "5") (pinfunction "IN_5") (pintype "unspecified"))
      (node (ref "C23") (pin "2") (pinfunction "2_2") (pintype "unspecified"))
      (node (ref "C32") (pin "2") (pinfunction "2_2") (pintype "unspecified"))
      (node (ref "C33") (pin "2") (pinfunction "2_2") (pintype "unspecified"))
      (node (ref "C35") (pin "2") (pinfunction "2_2") (pintype "unspecified"))
      (node (ref "C4") (pin "1") (pinfunction "1_1") (pintype "unspecified"))
      (node (ref "C57") (pin "1") (pinfunction "1_1") (pintype "unspecified"))
      (node (ref "C58") (pin "2") (pinfunction "2_2") (pintype "unspecified"))
      (node (ref "C61") (pin "1") (pinfunction "1_1") (pintype "unspecified"))
      (node (ref "C65") (pin "1") (pinfunction "1_1") (pintype "unspecified"))
      (node (ref "Q2") (pin "2") (pinfunction "S_2") (pintype "unspecified"))
      (node (ref "Q3") (pin "2") (pinfunction "S_2") (pintype "unspecified"))
      (node (ref "R20") (pin "2") (pinfunction "2_2") (pintype "unspecified"))
      (node (ref "R29") (pin "1") (pinfunction "1_1") (pintype "unspecified"))
      (node (ref "R30") (pin "1") (pinfunction "1_1") (pintype "unspecified"))
      (node (ref "U1") (pin "13") (pinfunction "VIN_13") (pintype "unspecified"))
      (node (ref "U1") (pin "14") (pinfunction "VIN_14") (pintype "unspecified"))
      (node (ref "U1") (pin "15") (pinfunction "VIN_15") (pintype "unspecified"))
      (node (ref "U1") (pin "16") (pinfunction "VIN_16") (pintype "unspecified"))
      (node (ref "U2") (pin "13") (pinfunction "VIN_13") (pintype "unspecified"))
      (node (ref "U2") (pin "14") (pinfunction "VIN_14") (pintype "unspecified"))
      (node (ref "U2") (pin "15") (pinfunction "VIN_15") (pintype "unspecified"))
      (node (ref "U2") (pin "16") (pinfunction "VIN_16") (pintype "unspecified"))
      (node (ref "U5") (pin "2") (pinfunction "2_2") (pintype "unspecified"))
    )
    (net (code "83") (name "VDD_SPI") (class "Default")
      (node (ref "C15") (pin "1") (pinfunction "1_1") (pintype "unspecified"))
      (node (ref "U4") (pin "18") (pinfunction "VDD_SPI_18") (pintype "unspecified"))
    )
    (net (code "84") (name "unconnected-(DC2-Pad3)") (class "Default")
      (node (ref "DC2") (pin "3") (pinfunction "3_3") (pintype "unspecified+no_connect"))
    )
    (net (code "85") (name "unconnected-(DC2-Pad4)") (class "Default")
      (node (ref "DC2") (pin "4") (pinfunction "4_4") (pintype "unspecified+no_connect"))
    )
    (net (code "86") (name "unconnected-(DC2-Pad5)") (class "Default")
      (node (ref "DC2") (pin "5") (pinfunction "5_5") (pintype "unspecified+no_connect"))
    )
    (net (code "87") (name "unconnected-(L4-Pad2)") (class "Default")
      (node (ref "L4") (pin "2") (pinfunction "2_2") (pintype "unspecified+no_connect"))
    )
    (net (code "88") (name "unconnected-(OLED1-NC-Pad7)") (class "Default")
      (node (ref "OLED1") (pin "7") (pinfunction "NC_7") (pintype "passive+no_connect"))
    )
    (net (code "89") (name "unconnected-(U1-GATE-Pad23)") (class "Default")
      (node (ref "U1") (pin "23") (pinfunction "GATE_23") (pintype "unspecified+no_connect"))
    )
    (net (code "90") (name "unconnected-(U1-NC-Pad17)") (class "Default")
      (node (ref "U1") (pin "17") (pinfunction "NC_17") (pintype "unspecified+no_connect"))
    )
    (net (code "91") (name "unconnected-(U1-VDD-Pad11)") (class "Default")
      (node (ref "U1") (pin "11") (pinfunction "VDD_11") (pintype "unspecified+no_connect"))
    )
    (net (code "92") (name "unconnected-(U2-GATE-Pad23)") (class "Default")
      (node (ref "U2") (pin "23") (pinfunction "GATE_23") (pintype "unspecified+no_connect"))
    )
    (net (code "93") (name "unconnected-(U2-NC-Pad17)") (class "Default")
      (node (ref "U2") (pin "17") (pinfunction "NC_17") (pintype "unspecified+no_connect"))
    )
    (net (code "94") (name "unconnected-(U2-VDD-Pad11)") (class "Default")
      (node (ref "U2") (pin "11") (pinfunction "VDD_11") (pintype "unspecified+no_connect"))
    )
    (net (code "95") (name "unconnected-(U3-HLED{slash}EN-Pad4)") (class "Default")
      (node (ref "U3") (pin "4") (pinfunction "HLED/EN_4") (pintype "unspecified+no_connect"))
    )
    (net (code "96") (name "unconnected-(U4-SPICLK-Pad22)") (class "Default")
      (node (ref "U4") (pin "22") (pinfunction "SPICLK_22") (pintype "unspecified+no_connect"))
    )
    (net (code "97") (name "unconnected-(U4-SPICS0-Pad21)") (class "Default")
      (node (ref "U4") (pin "21") (pinfunction "SPICS0_21") (pintype "unspecified+no_connect"))
    )
    (net (code "98") (name "unconnected-(U4-SPID-Pad23)") (class "Default")
      (node (ref "U4") (pin "23") (pinfunction "SPID_23") (pintype "unspecified+no_connect"))
    )
    (net (code "99") (name "unconnected-(U4-SPIHD-Pad19)") (class "Default")
      (node (ref "U4") (pin "19") (pinfunction "SPIHD_19") (pintype "unspecified+no_connect"))
    )
    (net (code "100") (name "unconnected-(U4-SPIQ-Pad24)") (class "Default")
      (node (ref "U4") (pin "24") (pinfunction "SPIQ_24") (pintype "unspecified+no_connect"))
    )
    (net (code "101") (name "unconnected-(U4-SPIWP-Pad20)") (class "Default")
      (node (ref "U4") (pin "20") (pinfunction "SPIWP_20") (pintype "unspecified+no_connect"))
    )
    (net (code "102") (name "unconnected-(U8-HLED{slash}EN-Pad4)") (class "Default")
      (node (ref "U8") (pin "4") (pinfunction "HLED/EN_4") (pintype "unspecified+no_connect"))
    )
    (net (code "103") (name "unconnected-(U9-ADC1-Pad16)") (class "Default")
      (node (ref "U9") (pin "16") (pinfunction "ADC1_16") (pintype "unspecified+no_connect"))
    )
    (net (code "104") (name "unconnected-(U9-ADC2-Pad15)") (class "Default")
      (node (ref "U9") (pin "15") (pinfunction "ADC2_15") (pintype "unspecified+no_connect"))
    )
    (net (code "105") (name "unconnected-(U9-ADC3-Pad13)") (class "Default")
      (node (ref "U9") (pin "13") (pinfunction "ADC3_13") (pintype "unspecified+no_connect"))
    )
    (net (code "106") (name "unconnected-(U9-INT1-Pad11)") (class "Default")
      (node (ref "U9") (pin "11") (pinfunction "INT1_11") (pintype "unspecified+no_connect"))
    )
    (net (code "107") (name "unconnected-(U9-INT2-Pad9)") (class "Default")
      (node (ref "U9") (pin "9") (pinfunction "INT2_9") (pintype "unspecified+no_connect"))
    )
    (net (code "108") (name "unconnected-(U9-NC-Pad2)") (class "Default")
      (node (ref "U9") (pin "2") (pinfunction "NC_2") (pintype "unspecified+no_connect"))
    )
    (net (code "109") (name "unconnected-(U9-NC-Pad3)") (class "Default")
      (node (ref "U9") (pin "3") (pinfunction "NC_3") (pintype "unspecified+no_connect"))
    )
    (net (code "110") (name "unconnected-(USB1-SBU1-PadA8)") (class "Default")
      (node (ref "USB1") (pin "A8") (pinfunction "SBU1_A8") (pintype "unspecified+no_connect"))
    )
    (net (code "111") (name "unconnected-(USB1-SBU2-PadB8)") (class "Default")
      (node (ref "USB1") (pin "B8") (pinfunction "SBU2_B8") (pintype "unspecified+no_connect"))
    )
  )
)
